# scheme.net
KiCad netlist of a schematic drawn in EAGLE
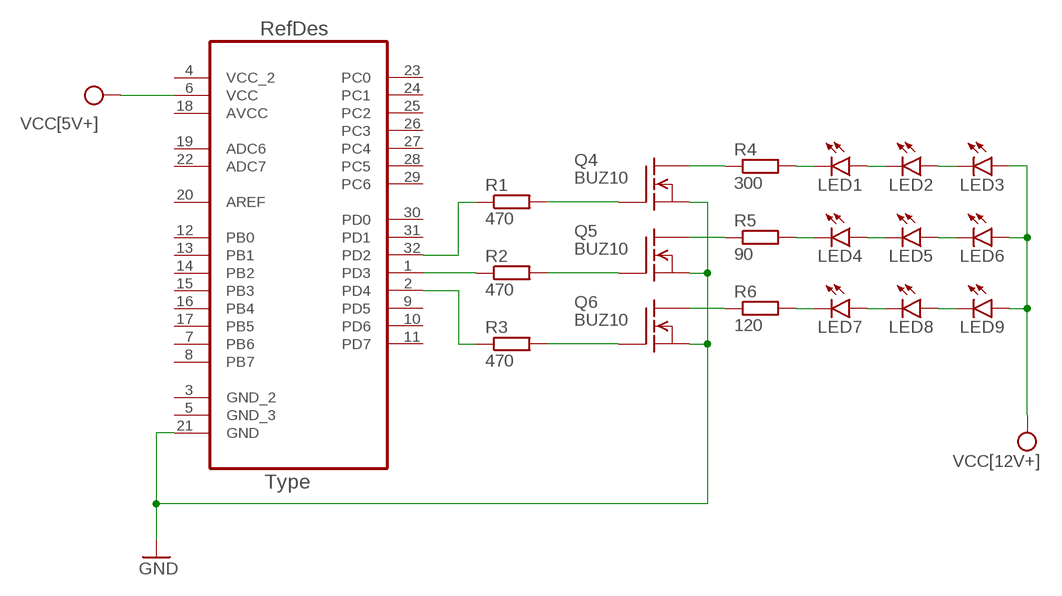
[diagram p0: schematic, sheet 1]

(export (version "E")
  (design (tool "Eeschema 10.0.6"))
  (components
    (comp (ref "LED1")
      (value "LED5MM")
      (footprint "eagle-import:LED5MM")
      (libsource (lib "eagle-import") (part "LED5MM"))
    )
    (comp (ref "LED2")
      (value "LED5MM")
      (footprint "eagle-import:LED5MM")
      (libsource (lib "eagle-import") (part "LED5MM"))
    )
    (comp (ref "LED3")
      (value "LED5MM")
      (footprint "eagle-import:LED5MM")
      (libsource (lib "eagle-import") (part "LED5MM"))
    )
    (comp (ref "LED4")
      (value "LED5MM")
      (footprint "eagle-import:LED5MM")
      (libsource (lib "eagle-import") (part "LED5MM"))
    )
    (comp (ref "LED5")
      (value "LED5MM")
      (footprint "eagle-import:LED5MM")
      (libsource (lib "eagle-import") (part "LED5MM"))
    )
    (comp (ref "LED6")
      (value "LED5MM")
      (footprint "eagle-import:LED5MM")
      (libsource (lib "eagle-import") (part "LED5MM"))
    )
    (comp (ref "LED7")
      (value "LED5MM")
      (footprint "eagle-import:LED5MM")
      (libsource (lib "eagle-import") (part "LED5MM"))
    )
    (comp (ref "LED8")
      (value "LED5MM")
      (footprint "eagle-import:LED5MM")
      (libsource (lib "eagle-import") (part "LED5MM"))
    )
    (comp (ref "LED9")
      (value "LED5MM")
      (footprint "eagle-import:LED5MM")
      (libsource (lib "eagle-import") (part "LED5MM"))
    )
    (comp (ref "Q4")
      (value "BUZ10")
      (footprint "eagle-import:TO220")
      (libsource (lib "eagle-import") (part "BUZ10"))
    )
    (comp (ref "Q5")
      (value "BUZ10")
      (footprint "eagle-import:TO220")
      (libsource (lib "eagle-import") (part "BUZ10"))
    )
    (comp (ref "Q6")
      (value "BUZ10")
      (footprint "eagle-import:TO220")
      (libsource (lib "eagle-import") (part "BUZ10"))
    )
    (comp (ref "R1")
      (value "470")
      (footprint "eagle-import:0204_7")
      (libsource (lib "eagle-import") (part "R-EU_0204/7"))
    )
    (comp (ref "R2")
      (value "470")
      (footprint "eagle-import:0204_7")
      (libsource (lib "eagle-import") (part "R-EU_0204/7"))
    )
    (comp (ref "R3")
      (value "470")
      (footprint "eagle-import:0204_7")
      (libsource (lib "eagle-import") (part "R-EU_0204/7"))
    )
    (comp (ref "R4")
      (value "300")
      (footprint "eagle-import:0204_7")
      (libsource (lib "eagle-import") (part "R-EU_0204/7"))
    )
    (comp (ref "R5")
      (value "90")
      (footprint "eagle-import:0204_7")
      (libsource (lib "eagle-import") (part "R-EU_0204/7"))
    )
    (comp (ref "R6")
      (value "120")
      (footprint "eagle-import:0204_7")
      (libsource (lib "eagle-import") (part "R-EU_0204/7"))
    )
    (comp (ref "U2")
      (value "ATMEGA328P-AU")
      (footprint "eagle-import:QFP80P900X900X120-32N")
      (libsource (lib "eagle-import") (part "ATMEGA328P-AU"))
    )
  )
  (nets
    (net (code "1") (name "/AVCC") (class "Default")
      (node (ref "U2") (pin "18") (pinfunction "AVCC_18") (pintype "power_in"))
    )
    (net (code "2") (name "/VCC_2") (class "Default")
      (node (ref "U2") (pin "4") (pinfunction "VCC_2_4") (pintype "power_in"))
    )
    (net (code "3") (name "GND") (class "Default")
      (node (ref "Q4") (pin "3") (pinfunction "S_3") (pintype "passive"))
      (node (ref "Q5") (pin "3") (pinfunction "S_3") (pintype "passive"))
      (node (ref "Q6") (pin "3") (pinfunction "S_3") (pintype "passive"))
      (node (ref "U2") (pin "21") (pinfunction "GND_21") (pintype "passive"))
    )
    (net (code "4") (name "Net-(LED1-C)") (class "Default")
      (node (ref "LED1") (pin "K") (pinfunction "C_K") (pintype "passive"))
      (node (ref "R4") (pin "2") (pinfunction "2_2") (pintype "passive"))
    )
    (net (code "5") (name "Net-(LED2-C)") (class "Default")
      (node (ref "LED1") (pin "A") (pinfunction "A_A") (pintype "passive"))
      (node (ref "LED2") (pin "K") (pinfunction "C_K") (pintype "passive"))
    )
    (net (code "6") (name "Net-(LED3-C)") (class "Default")
      (node (ref "LED2") (pin "A") (pinfunction "A_A") (pintype "passive"))
      (node (ref "LED3") (pin "K") (pinfunction "C_K") (pintype "passive"))
    )
    (net (code "7") (name "Net-(LED4-C)") (class "Default")
      (node (ref "LED4") (pin "K") (pinfunction "C_K") (pintype "passive"))
      (node (ref "R5") (pin "2") (pinfunction "2_2") (pintype "passive"))
    )
    (net (code "8") (name "Net-(LED5-C)") (class "Default")
      (node (ref "LED4") (pin "A") (pinfunction "A_A") (pintype "passive"))
      (node (ref "LED5") (pin "K") (pinfunction "C_K") (pintype "passive"))
    )
    (net (code "9") (name "Net-(LED6-C)") (class "Default")
      (node (ref "LED5") (pin "A") (pinfunction "A_A") (pintype "passive"))
      (node (ref "LED6") (pin "K") (pinfunction "C_K") (pintype "passive"))
    )
    (net (code "10") (name "Net-(LED7-C)") (class "Default")
      (node (ref "LED7") (pin "K") (pinfunction "C_K") (pintype "passive"))
      (node (ref "R6") (pin "2") (pinfunction "2_2") (pintype "passive"))
    )
    (net (code "11") (name "Net-(LED8-C)") (class "Default")
      (node (ref "LED7") (pin "A") (pinfunction "A_A") (pintype "passive"))
      (node (ref "LED8") (pin "K") (pinfunction "C_K") (pintype "passive"))
    )
    (net (code "12") (name "Net-(LED9-C)") (class "Default")
      (node (ref "LED8") (pin "A") (pinfunction "A_A") (pintype "passive"))
      (node (ref "LED9") (pin "K") (pinfunction "C_K") (pintype "passive"))
    )
    (net (code "13") (name "Net-(Q4-D)") (class "Default")
      (node (ref "Q4") (pin "2") (pinfunction "D_2") (pintype "passive"))
      (node (ref "R4") (pin "1") (pinfunction "1_1") (pintype "passive"))
    )
    (net (code "14") (name "Net-(Q4-G)") (class "Default")
      (node (ref "Q4") (pin "1") (pinfunction "G_1") (pintype "passive"))
      (node (ref "R1") (pin "2") (pinfunction "2_2") (pintype "passive"))
    )
    (net (code "15") (name "Net-(Q5-D)") (class "Default")
      (node (ref "Q5") (pin "2") (pinfunction "D_2") (pintype "passive"))
      (node (ref "R5") (pin "1") (pinfunction "1_1") (pintype "passive"))
    )
    (net (code "16") (name "Net-(Q5-G)") (class "Default")
      (node (ref "Q5") (pin "1") (pinfunction "G_1") (pintype "passive"))
      (node (ref "R2") (pin "2") (pinfunction "2_2") (pintype "passive"))
    )
    (net (code "17") (name "Net-(Q6-D)") (class "Default")
      (node (ref "Q6") (pin "2") (pinfunction "D_2") (pintype "passive"))
      (node (ref "R6") (pin "1") (pinfunction "1_1") (pintype "passive"))
    )
    (net (code "18") (name "Net-(Q6-G)") (class "Default")
      (node (ref "Q6") (pin "1") (pinfunction "G_1") (pintype "passive"))
      (node (ref "R3") (pin "2") (pinfunction "2_2") (pintype "passive"))
    )
    (net (code "19") (name "Net-(U2-PD2)") (class "Default")
      (node (ref "R1") (pin "1") (pinfunction "1_1") (pintype "passive"))
      (node (ref "U2") (pin "32") (pinfunction "PD2_32") (pintype "bidirectional"))
    )
    (net (code "20") (name "Net-(U2-PD3)") (class "Default")
      (node (ref "R2") (pin "1") (pinfunction "1_1") (pintype "passive"))
      (node (ref "U2") (pin "1") (pinfunction "PD3_1") (pintype "bidirectional"))
    )
    (net (code "21") (name "Net-(U2-PD4)") (class "Default")
      (node (ref "R3") (pin "1") (pinfunction "1_1") (pintype "passive"))
      (node (ref "U2") (pin "2") (pinfunction "PD4_2") (pintype "bidirectional"))
    )
    (net (code "22") (name "VCC[12V+]") (class "Default")
      (node (ref "LED3") (pin "A") (pinfunction "A_A") (pintype "passive"))
      (node (ref "LED6") (pin "A") (pinfunction "A_A") (pintype "passive"))
      (node (ref "LED9") (pin "A") (pinfunction "A_A") (pintype "passive"))
      (node (ref "U2") (pin "6") (pinfunction "VCC_6") (pintype "power_in"))
    )
    (net (code "23") (name "unconnected-(U2-ADC6-Pad19)") (class "Default")
      (node (ref "U2") (pin "19") (pinfunction "ADC6_19") (pintype "input"))
    )
    (net (code "24") (name "unconnected-(U2-ADC7-Pad22)") (class "Default")
      (node (ref "U2") (pin "22") (pinfunction "ADC7_22") (pintype "input"))
    )
    (net (code "25") (name "unconnected-(U2-AREF-Pad20)") (class "Default")
      (node (ref "U2") (pin "20") (pinfunction "AREF_20") (pintype "input"))
    )
    (net (code "26") (name "unconnected-(U2-GND_2-Pad3)") (class "Default")
      (node (ref "U2") (pin "3") (pinfunction "GND_2_3") (pintype "passive"))
    )
    (net (code "27") (name "unconnected-(U2-GND_3-Pad5)") (class "Default")
      (node (ref "U2") (pin "5") (pinfunction "GND_3_5") (pintype "passive"))
    )
    (net (code "28") (name "unconnected-(U2-PB0-Pad12)") (class "Default")
      (node (ref "U2") (pin "12") (pinfunction "PB0_12") (pintype "bidirectional"))
    )
    (net (code "29") (name "unconnected-(U2-PB1-Pad13)") (class "Default")
      (node (ref "U2") (pin "13") (pinfunction "PB1_13") (pintype "bidirectional"))
    )
    (net (code "30") (name "unconnected-(U2-PB2-Pad14)") (class "Default")
      (node (ref "U2") (pin "14") (pinfunction "PB2_14") (pintype "bidirectional"))
    )
    (net (code "31") (name "unconnected-(U2-PB3-Pad15)") (class "Default")
      (node (ref "U2") (pin "15") (pinfunction "PB3_15") (pintype "bidirectional"))
    )
    (net (code "32") (name "unconnected-(U2-PB4-Pad16)") (class "Default")
      (node (ref "U2") (pin "16") (pinfunction "PB4_16") (pintype "bidirectional"))
    )
    (net (code "33") (name "unconnected-(U2-PB5-Pad17)") (class "Default")
      (node (ref "U2") (pin "17") (pinfunction "PB5_17") (pintype "bidirectional"))
    )
    (net (code "34") (name "unconnected-(U2-PB6-Pad7)") (class "Default")
      (node (ref "U2") (pin "7") (pinfunction "PB6_7") (pintype "bidirectional"))
    )
    (net (code "35") (name "unconnected-(U2-PB7-Pad8)") (class "Default")
      (node (ref "U2") (pin "8") (pinfunction "PB7_8") (pintype "bidirectional"))
    )
    (net (code "36") (name "unconnected-(U2-PC0-Pad23)") (class "Default")
      (node (ref "U2") (pin "23") (pinfunction "PC0_23") (pintype "bidirectional"))
    )
    (net (code "37") (name "unconnected-(U2-PC1-Pad24)") (class "Default")
      (node (ref "U2") (pin "24") (pinfunction "PC1_24") (pintype "bidirectional"))
    )
    (net (code "38") (name "unconnected-(U2-PC2-Pad25)") (class "Default")
      (node (ref "U2") (pin "25") (pinfunction "PC2_25") (pintype "bidirectional"))
    )
    (net (code "39") (name "unconnected-(U2-PC3-Pad26)") (class "Default")
      (node (ref "U2") (pin "26") (pinfunction "PC3_26") (pintype "bidirectional"))
    )
    (net (code "40") (name "unconnected-(U2-PC4-Pad27)") (class "Default")
      (node (ref "U2") (pin "27") (pinfunction "PC4_27") (pintype "bidirectional"))
    )
    (net (code "41") (name "unconnected-(U2-PC5-Pad28)") (class "Default")
      (node (ref "U2") (pin "28") (pinfunction "PC5_28") (pintype "bidirectional"))
    )
    (net (code "42") (name "unconnected-(U2-PC6-Pad29)") (class "Default")
      (node (ref "U2") (pin "29") (pinfunction "PC6_29") (pintype "bidirectional"))
    )
    (net (code "43") (name "unconnected-(U2-PD0-Pad30)") (class "Default")
      (node (ref "U2") (pin "30") (pinfunction "PD0_30") (pintype "bidirectional"))
    )
    (net (code "44") (name "unconnected-(U2-PD1-Pad31)") (class "Default")
      (node (ref "U2") (pin "31") (pinfunction "PD1_31") (pintype "bidirectional"))
    )
    (net (code "45") (name "unconnected-(U2-PD5-Pad9)") (class "Default")
      (node (ref "U2") (pin "9") (pinfunction "PD5_9") (pintype "bidirectional"))
    )
    (net (code "46") (name "unconnected-(U2-PD6-Pad10)") (class "Default")
      (node (ref "U2") (pin "10") (pinfunction "PD6_10") (pintype "bidirectional"))
    )
    (net (code "47") (name "unconnected-(U2-PD7-Pad11)") (class "Default")
      (node (ref "U2") (pin "11") (pinfunction "PD7_11") (pintype "bidirectional"))
    )
  )
)
